# Direct_Digital_IO.net
KiCad netlist of a schematic drawn in Altium Designer
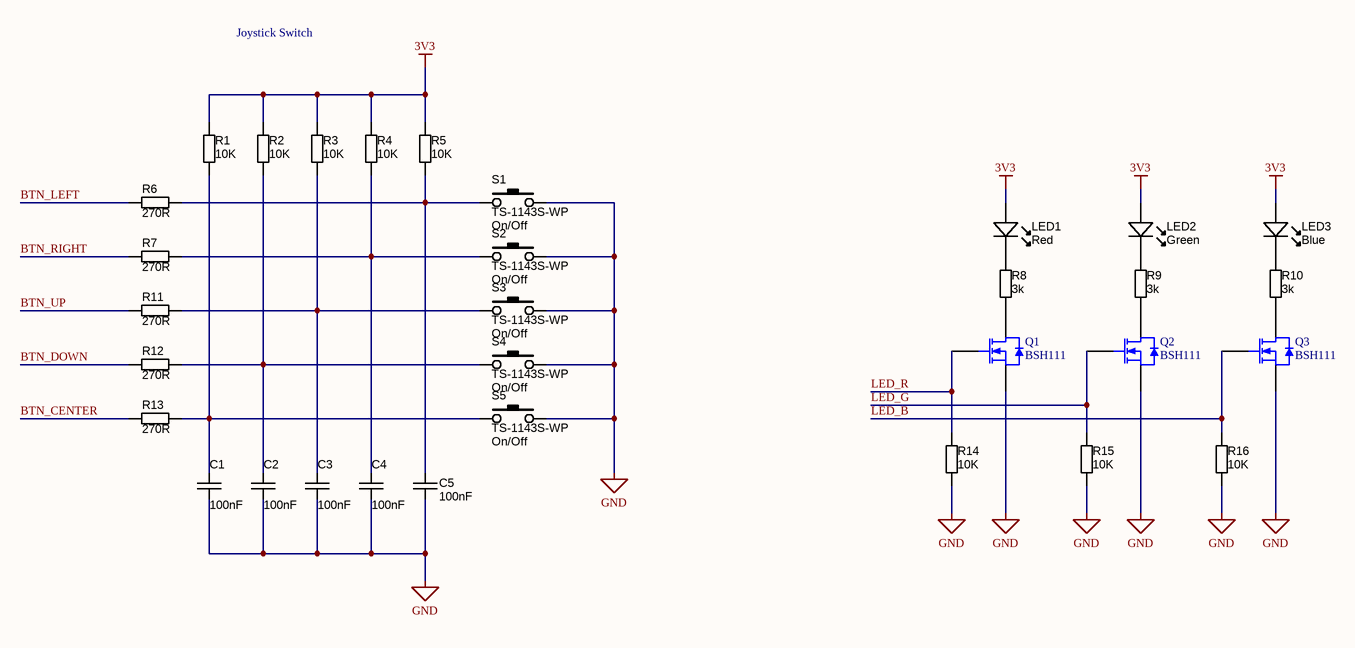
[diagram p0: Direct Digital IO.SchDoc]

(export (version "E")
  (design (tool "Eeschema 10.0.6"))
  (components
    (comp (ref "C1")
      (value "100nF")
      (footprint "CAPC1005N")
      (description "Capacitor SMD Cer 100nF 10% 50V X7R 0805")
      (fields (field (name "TOLERANCE") "?0%") (field (name "Comment") "approved sub OK"))
      (libsource (lib "PBL - Capacitors") (part "CAPC_100n_0805"))
    )
    (comp (ref "C2")
      (value "100nF")
      (footprint "CAPC1005N")
      (description "Capacitor SMD Cer 100nF 10% 50V X7R 0805")
      (fields (field (name "TOLERANCE") "?0%") (field (name "Comment") "approved sub OK"))
      (libsource (lib "PBL - Capacitors") (part "CAPC_100n_0805"))
    )
    (comp (ref "C3")
      (value "100nF")
      (footprint "CAPC1005N")
      (description "Capacitor SMD Cer 100nF 10% 50V X7R 0805")
      (fields (field (name "TOLERANCE") "?0%") (field (name "Comment") "approved sub OK"))
      (libsource (lib "PBL - Capacitors") (part "CAPC_100n_0805"))
    )
    (comp (ref "C4")
      (value "100nF")
      (footprint "CAPC1005N")
      (description "Capacitor SMD Cer 100nF 10% 50V X7R 0805")
      (fields (field (name "TOLERANCE") "?0%") (field (name "Comment") "approved sub OK"))
      (libsource (lib "PBL - Capacitors") (part "CAPC_100n_0805"))
    )
    (comp (ref "C5")
      (value "100nF")
      (footprint "CAPC1005N")
      (description "Capacitor SMD Cer 100nF 10% 50V X7R 0805")
      (fields (field (name "TOLERANCE") "?0%") (field (name "Comment") "approved sub OK"))
      (libsource (lib "PBL - Capacitors") (part "CAPC_100n_0805"))
    )
    (comp (ref "LED1")
      (value "~")
      (footprint "LED-0603-GREEN")
      (description "LED 0805 SMD Red 6mcd 621nm")
      (fields (field (name "COLOR") "Red"))
      (libsource (lib "PBL - Light Sources") (part "LED_SMD_Red_0805_6mcd"))
    )
    (comp (ref "LED2")
      (value "~")
      (footprint "LED-0603-GREEN")
      (description "LED, 0805 SMD, Green")
      (fields (field (name "COLOR") "Green"))
      (libsource (lib "PBL - Light Sources") (part "LED_SMD_Green_0805_6mcd"))
    )
    (comp (ref "LED3")
      (value "Blue")
      (footprint "LED-0603-GREEN")
      (description "LED 0805 SMD Blue 100mcd 470nm")
      (fields (field (name "COLOR") "Blue"))
      (libsource (lib "PBL - Light Sources") (part "LED_SMD_Blue_0805_100mcd"))
    )
    (comp (ref "Q1")
      (value "BSH111")
      (footprint "SOT23_N")
      (description "N-channel Enhancement Mode MOSFET")
      (fields (field (name "PUBLISHER") "Altium Limited"))
      (libsource (lib "Philips Discrete MOSFET - Low Power") (part "BSH103"))
    )
    (comp (ref "Q2")
      (value "BSH111")
      (footprint "SOT23_N")
      (description "N-channel Enhancement Mode MOSFET")
      (fields (field (name "PUBLISHER") "Altium Limited"))
      (libsource (lib "Philips Discrete MOSFET - Low Power") (part "BSH103"))
    )
    (comp (ref "Q3")
      (value "BSH111")
      (footprint "SOT23_N")
      (description "N-channel Enhancement Mode MOSFET")
      (fields (field (name "PUBLISHER") "Altium Limited"))
      (libsource (lib "Philips Discrete MOSFET - Low Power") (part "BSH103"))
    )
    (comp (ref "R1")
      (value "10K")
      (footprint "RESC1005N")
      (description "Resistor SMD chip 10k Ohm 0.125W 5% 0805")
      (fields (field (name "TOLERANCE") "?%") (field (name "Comment") "Thick Film"))
      (libsource (lib "PBL - Resistors") (part "RES_10K_0805_5%"))
    )
    (comp (ref "R2")
      (value "10K")
      (footprint "RESC1005N")
      (description "Resistor SMD chip 10k Ohm 0.125W 5% 0805")
      (fields (field (name "TOLERANCE") "?%") (field (name "Comment") "Thick Film"))
      (libsource (lib "PBL - Resistors") (part "RES_10K_0805_5%"))
    )
    (comp (ref "R3")
      (value "10K")
      (footprint "RESC1005N")
      (description "Resistor SMD chip 10k Ohm 0.125W 5% 0805")
      (fields (field (name "TOLERANCE") "?%") (field (name "Comment") "Thick Film"))
      (libsource (lib "PBL - Resistors") (part "RES_10K_0805_5%"))
    )
    (comp (ref "R4")
      (value "10K")
      (footprint "RESC1005N")
      (description "Resistor SMD chip 10k Ohm 0.125W 5% 0805")
      (fields (field (name "TOLERANCE") "?%") (field (name "Comment") "Thick Film"))
      (libsource (lib "PBL - Resistors") (part "RES_10K_0805_5%"))
    )
    (comp (ref "R5")
      (value "10K")
      (footprint "RESC1005N")
      (description "Resistor SMD chip 10k Ohm 0.125W 5% 0805")
      (fields (field (name "TOLERANCE") "?%") (field (name "Comment") "Thick Film"))
      (libsource (lib "PBL - Resistors") (part "RES_10K_0805_5%"))
    )
    (comp (ref "R6")
      (value "270R")
      (footprint "RESC1005N")
      (description "Resistor SMD chip 330 Ohm 0.063W 5% 0402")
      (fields (field (name "TOLERANCE") "?%") (field (name "Comment") "Thick Film"))
      (libsource (lib "") (part "RES_330R_0402_5%_1"))
    )
    (comp (ref "R7")
      (value "270R")
      (footprint "RESC1005N")
      (description "Resistor SMD chip 330 Ohm 0.063W 5% 0402")
      (fields (field (name "TOLERANCE") "?%") (field (name "Comment") "Thick Film"))
      (libsource (lib "PBL - Resistors") (part "RES_330R_0402_5%"))
    )
    (comp (ref "R8")
      (value "3k")
      (footprint "RESC1005N")
      (description "Resistor SMD chip 10k Ohm 0.125W 5% 0805")
      (fields (field (name "TOLERANCE") "?%") (field (name "Comment") "Thick Film"))
      (libsource (lib "") (part "RES_10K_0805_5%_1"))
    )
    (comp (ref "R9")
      (value "3k")
      (footprint "RESC1005N")
      (description "Resistor SMD chip 10k Ohm 0.125W 5% 0805")
      (fields (field (name "TOLERANCE") "?%") (field (name "Comment") "Thick Film"))
      (libsource (lib "PBL - Resistors") (part "RES_10K_0805_5%"))
    )
    (comp (ref "R10")
      (value "3k")
      (footprint "RESC1005N")
      (description "Resistor SMD chip 10k Ohm 0.125W 5% 0805")
      (fields (field (name "TOLERANCE") "?%") (field (name "Comment") "Thick Film"))
      (libsource (lib "PBL - Resistors") (part "RES_10K_0805_5%"))
    )
    (comp (ref "R11")
      (value "270R")
      (footprint "RESC1005N")
      (description "Resistor SMD chip 330 Ohm 0.063W 5% 0402")
      (fields (field (name "TOLERANCE") "?%") (field (name "Comment") "Thick Film"))
      (libsource (lib "PBL - Resistors") (part "RES_330R_0402_5%"))
    )
    (comp (ref "R12")
      (value "270R")
      (footprint "RESC1005N")
      (description "Resistor SMD chip 330 Ohm 0.063W 5% 0402")
      (fields (field (name "TOLERANCE") "?%") (field (name "Comment") "Thick Film"))
      (libsource (lib "PBL - Resistors") (part "RES_330R_0402_5%"))
    )
    (comp (ref "R13")
      (value "270R")
      (footprint "RESC1005N")
      (description "Resistor SMD chip 330 Ohm 0.063W 5% 0402")
      (fields (field (name "TOLERANCE") "?%") (field (name "Comment") "Thick Film"))
      (libsource (lib "") (part "RES_330R_0402_5%_1"))
    )
    (comp (ref "R14")
      (value "10K")
      (footprint "RESC1005N")
      (description "Resistor SMD chip 10k Ohm 0.125W 5% 0805")
      (fields (field (name "TOLERANCE") "?%") (field (name "Comment") "Thick Film"))
      (libsource (lib "") (part "RES_10K_0805_5%_1"))
    )
    (comp (ref "R15")
      (value "10K")
      (footprint "RESC1005N")
      (description "Resistor SMD chip 10k Ohm 0.125W 5% 0805")
      (fields (field (name "TOLERANCE") "?%") (field (name "Comment") "Thick Film"))
      (libsource (lib "PBL - Resistors") (part "RES_10K_0805_5%"))
    )
    (comp (ref "R16")
      (value "10K")
      (footprint "RESC1005N")
      (description "Resistor SMD chip 10k Ohm 0.125W 5% 0805")
      (fields (field (name "TOLERANCE") "?%") (field (name "Comment") "Thick Film"))
      (libsource (lib "PBL - Resistors") (part "RES_10K_0805_5%"))
    )
    (comp (ref "S1")
      (value "TS-1143S-WP")
      (footprint "TS-1143S")
      (description "Switch SMD Tact 4.3mm Stem")
      (fields (field (name "FUNCTION") "On/Off"))
      (libsource (lib "PBL - Switches") (part "SW_SMD_PB_4.3mm"))
    )
    (comp (ref "S2")
      (value "TS-1143S-WP")
      (footprint "TS-1143S")
      (description "Switch SMD Tact 4.3mm Stem")
      (fields (field (name "FUNCTION") "On/Off"))
      (libsource (lib "PBL - Switches") (part "SW_SMD_PB_4.3mm"))
    )
    (comp (ref "S3")
      (value "TS-1143S-WP")
      (footprint "TS-1143S")
      (description "Switch SMD Tact 4.3mm Stem")
      (fields (field (name "FUNCTION") "On/Off"))
      (libsource (lib "PBL - Switches") (part "SW_SMD_PB_4.3mm"))
    )
    (comp (ref "S4")
      (value "TS-1143S-WP")
      (footprint "TS-1143S")
      (description "Switch SMD Tact 4.3mm Stem")
      (fields (field (name "FUNCTION") "On/Off"))
      (libsource (lib "PBL - Switches") (part "SW_SMD_PB_4.3mm"))
    )
    (comp (ref "S5")
      (value "TS-1143S-WP")
      (footprint "TS-1143S")
      (description "Switch SMD Tact 4.3mm Stem")
      (fields (field (name "FUNCTION") "On/Off"))
      (libsource (lib "PBL - Switches") (part "SW_SMD_PB_4.3mm"))
    )
  )
  (nets
    (net (code "1") (name "/BTN_CENTER") (class "Default")
      (node (ref "R13") (pin "2") (pinfunction "2_2") (pintype "passive"))
    )
    (net (code "2") (name "/BTN_DOWN") (class "Default")
      (node (ref "R12") (pin "1") (pinfunction "1_1") (pintype "passive"))
    )
    (net (code "3") (name "/BTN_LEFT") (class "Default")
      (node (ref "R6") (pin "2") (pinfunction "2_2") (pintype "passive"))
    )
    (net (code "4") (name "/BTN_RIGHT") (class "Default")
      (node (ref "R7") (pin "1") (pinfunction "1_1") (pintype "passive"))
    )
    (net (code "5") (name "/BTN_UP") (class "Default")
      (node (ref "R11") (pin "1") (pinfunction "1_1") (pintype "passive"))
    )
    (net (code "6") (name "/LED_B") (class "Default")
      (node (ref "Q3") (pin "1") (pinfunction "G_1") (pintype "passive"))
      (node (ref "R16") (pin "1") (pinfunction "1_1") (pintype "passive"))
    )
    (net (code "7") (name "/LED_G") (class "Default")
      (node (ref "Q2") (pin "1") (pinfunction "G_1") (pintype "passive"))
      (node (ref "R15") (pin "1") (pinfunction "1_1") (pintype "passive"))
    )
    (net (code "8") (name "/LED_R") (class "Default")
      (node (ref "Q1") (pin "1") (pinfunction "G_1") (pintype "passive"))
      (node (ref "R14") (pin "2") (pinfunction "2_2") (pintype "passive"))
    )
    (net (code "9") (name "3V3") (class "Default")
      (node (ref "LED1") (pin "A") (pinfunction "A_A") (pintype "passive"))
      (node (ref "LED2") (pin "A") (pinfunction "A_A") (pintype "passive"))
      (node (ref "LED3") (pin "A") (pinfunction "A_A") (pintype "passive"))
      (node (ref "R1") (pin "1") (pinfunction "1_1") (pintype "passive"))
      (node (ref "R2") (pin "1") (pinfunction "1_1") (pintype "passive"))
      (node (ref "R3") (pin "1") (pinfunction "1_1") (pintype "passive"))
      (node (ref "R4") (pin "1") (pinfunction "1_1") (pintype "passive"))
      (node (ref "R5") (pin "1") (pinfunction "1_1") (pintype "passive"))
    )
    (net (code "10") (name "GND") (class "Default")
      (node (ref "C1") (pin "2") (pintype "passive"))
      (node (ref "C2") (pin "2") (pintype "passive"))
      (node (ref "C3") (pin "2") (pintype "passive"))
      (node (ref "C4") (pin "2") (pintype "passive"))
      (node (ref "C5") (pin "2") (pintype "passive"))
      (node (ref "Q1") (pin "2") (pinfunction "S_2") (pintype "passive"))
      (node (ref "Q2") (pin "2") (pinfunction "S_2") (pintype "passive"))
      (node (ref "Q3") (pin "2") (pinfunction "S_2") (pintype "passive"))
      (node (ref "R14") (pin "1") (pinfunction "1_1") (pintype "passive"))
      (node (ref "R15") (pin "2") (pinfunction "2_2") (pintype "passive"))
      (node (ref "R16") (pin "2") (pinfunction "2_2") (pintype "passive"))
      (node (ref "S1") (pin "2") (pintype "passive"))
      (node (ref "S2") (pin "2") (pintype "passive"))
      (node (ref "S3") (pin "2") (pintype "passive"))
      (node (ref "S4") (pin "2") (pintype "passive"))
      (node (ref "S5") (pin "2") (pintype "passive"))
    )
    (net (code "11") (name "Net-(C1-Pad1)") (class "Default")
      (node (ref "C1") (pin "1") (pintype "passive"))
      (node (ref "R1") (pin "2") (pinfunction "2_2") (pintype "passive"))
      (node (ref "R13") (pin "1") (pinfunction "1_1") (pintype "passive"))
      (node (ref "S5") (pin "1") (pintype "passive"))
    )
    (net (code "12") (name "Net-(C2-Pad1)") (class "Default")
      (node (ref "C2") (pin "1") (pintype "passive"))
      (node (ref "R12") (pin "2") (pinfunction "2_2") (pintype "passive"))
      (node (ref "R2") (pin "2") (pinfunction "2_2") (pintype "passive"))
      (node (ref "S4") (pin "1") (pintype "passive"))
    )
    (net (code "13") (name "Net-(C3-Pad1)") (class "Default")
      (node (ref "C3") (pin "1") (pintype "passive"))
      (node (ref "R11") (pin "2") (pinfunction "2_2") (pintype "passive"))
      (node (ref "R3") (pin "2") (pinfunction "2_2") (pintype "passive"))
      (node (ref "S3") (pin "1") (pintype "passive"))
    )
    (net (code "14") (name "Net-(C4-Pad1)") (class "Default")
      (node (ref "C4") (pin "1") (pintype "passive"))
      (node (ref "R4") (pin "2") (pinfunction "2_2") (pintype "passive"))
      (node (ref "R7") (pin "2") (pinfunction "2_2") (pintype "passive"))
      (node (ref "S2") (pin "1") (pintype "passive"))
    )
    (net (code "15") (name "Net-(C5-Pad1)") (class "Default")
      (node (ref "C5") (pin "1") (pintype "passive"))
      (node (ref "R5") (pin "2") (pinfunction "2_2") (pintype "passive"))
      (node (ref "R6") (pin "1") (pinfunction "1_1") (pintype "passive"))
      (node (ref "S1") (pin "1") (pintype "passive"))
    )
    (net (code "16") (name "Net-(LED1-PadK)") (class "Default")
      (node (ref "LED1") (pin "K") (pinfunction "K_K") (pintype "passive"))
      (node (ref "R8") (pin "2") (pinfunction "2_2") (pintype "passive"))
    )
    (net (code "17") (name "Net-(LED2-PadK)") (class "Default")
      (node (ref "LED2") (pin "K") (pinfunction "K_K") (pintype "passive"))
      (node (ref "R9") (pin "1") (pinfunction "1_1") (pintype "passive"))
    )
    (net (code "18") (name "Net-(LED3-PadK)") (class "Default")
      (node (ref "LED3") (pin "K") (pinfunction "K_K") (pintype "passive"))
      (node (ref "R10") (pin "1") (pinfunction "1_1") (pintype "passive"))
    )
    (net (code "19") (name "Net-(Q1-D)") (class "Default")
      (node (ref "Q1") (pin "3") (pinfunction "D_3") (pintype "passive"))
      (node (ref "R8") (pin "1") (pinfunction "1_1") (pintype "passive"))
    )
    (net (code "20") (name "Net-(Q2-D)") (class "Default")
      (node (ref "Q2") (pin "3") (pinfunction "D_3") (pintype "passive"))
      (node (ref "R9") (pin "2") (pinfunction "2_2") (pintype "passive"))
    )
    (net (code "21") (name "Net-(Q3-D)") (class "Default")
      (node (ref "Q3") (pin "3") (pinfunction "D_3") (pintype "passive"))
      (node (ref "R10") (pin "2") (pinfunction "2_2") (pintype "passive"))
    )
  )
)
